# Fuente.net
KiCad netlist of a schematic drawn in Altium Designer
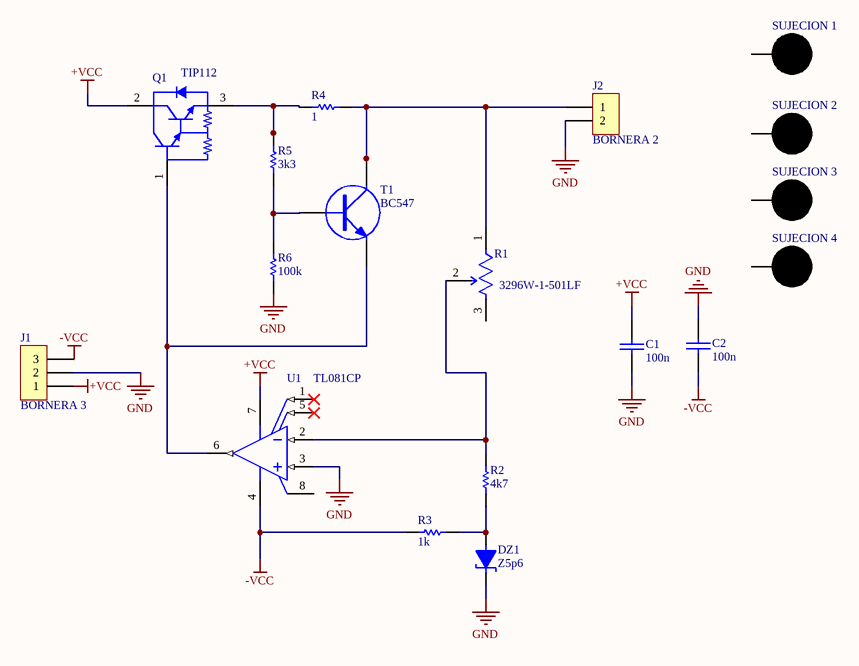
[diagram p0: Fuente.SchDoc]

(export (version "E")
  (design (tool "Eeschema 10.0.6"))
  (components
    (comp (ref "C1") (value "100n") (footprint "CAP200") (libsource (lib "LIB PIO IX") (part "CAP")))
    (comp (ref "C2") (value "100n") (footprint "CAP200") (libsource (lib "LIB PIO IX") (part "CAP")))
    (comp (ref "DZ1") (value "Z5p6") (footprint "DO41") (libsource (lib "LIB PIO IX") (part "DIODO ZENER")))
    (comp (ref "J1")
      (value "BORNERA 3")
      (footprint "BORNERA3")
      (libsource (lib "LIB PIO IX") (part "BORNERA 3"))
    )
    (comp (ref "J2")
      (value "BORNERA 2")
      (footprint "BORNERA2")
      (libsource (lib "LIB PIO IX") (part "BORNERA 2"))
    )
    (comp (ref "Q1")
      (value "TIP112")
      (footprint "ONSC-TO-220-3-221A-09")
      (description "Plastic Medium-Power, Complementary Silicon Transistor, 3-Pin TO-220, Tube")
      (fields (field (name "MANUFACTURER") "On Semiconductor"))
      (libsource (lib "Altium Content Vault") (part "ONSC-DT-NPN-B1C2E3-3_A"))
    )
    (comp (ref "R1")
      (value "3296W-1-501LF")
      (footprint "FP-3296W-MFG")
      (description "TRIMMER 500 OHM 0.5W PC PIN TOP")
      (fields (field (name "TOLERANCE") "10%"))
      (libsource (lib "Altium Content Vault") (part "2dcfd2547301a7d3209a5e99acfd772"))
    )
    (comp (ref "R2") (value "4k7") (footprint "RES400") (libsource (lib "LIB PIO IX") (part "RES")))
    (comp (ref "R3") (value "1k") (footprint "RES400") (libsource (lib "LIB PIO IX") (part "RES")))
    (comp (ref "R4") (value "1") (footprint "RES600") (libsource (lib "LIB PIO IX") (part "RES")))
    (comp (ref "R5") (value "3k3") (footprint "RES400") (libsource (lib "LIB PIO IX") (part "RES")))
    (comp (ref "R6") (value "100k") (footprint "RES400") (libsource (lib "LIB PIO IX") (part "RES")))
    (comp (ref "SUJECION 1")
      (value "~")
      (footprint "SUJECION (5.00MM - 3.50MM)")
      (libsource (lib "LIB2013") (part "SUJECION"))
    )
    (comp (ref "SUJECION 2")
      (value "~")
      (footprint "SUJECION (5.00MM - 3.50MM)")
      (libsource (lib "LIB2013") (part "SUJECION"))
    )
    (comp (ref "SUJECION 3")
      (value "~")
      (footprint "SUJECION (5.00MM - 3.50MM)")
      (libsource (lib "LIB2013") (part "SUJECION"))
    )
    (comp (ref "SUJECION 4")
      (value "~")
      (footprint "SUJECION (5.00MM - 3.50MM)")
      (libsource (lib "LIB2013") (part "SUJECION"))
    )
    (comp (ref "T1")
      (value "BC547")
      (footprint "TO92")
      (libsource (lib "LIB PIO IX") (part "TRANSISTOR NPN"))
    )
    (comp (ref "U1")
      (value "TL081CP")
      (footprint "P0008A")
      (description "JFET-Input Operational Amplifier, 7 to 36 V, 0 to 70 degC, 8-pin DIP (P8), Pb-Free (RoHS)")
      (fields (field (name "MANUFACTURER") "Texas Instruments"))
      (libsource (lib "Altium Content Vault") (part "TI-AMP-S5-2-8"))
    )
  )
  (nets
    (net (code "1") (name "+VCC") (class "Default")
      (node (ref "C1") (pin "1") (pinfunction "1_1") (pintype "passive"))
      (node (ref "J1") (pin "1") (pinfunction "1_1") (pintype "passive"))
      (node (ref "Q1") (pin "2") (pinfunction "C_2") (pintype "passive"))
      (node (ref "U1") (pin "7") (pinfunction "VCC+_7") (pintype "power_in"))
    )
    (net (code "2") (name "-VCC") (class "Default")
      (node (ref "C2") (pin "2") (pinfunction "2_2") (pintype "passive"))
      (node (ref "J1") (pin "3") (pinfunction "3_3") (pintype "passive"))
      (node (ref "R3") (pin "1") (pinfunction "1_1") (pintype "passive"))
      (node (ref "U1") (pin "4") (pinfunction "VCC-_4") (pintype "power_in"))
    )
    (net (code "3") (name "GND") (class "Default")
      (node (ref "C1") (pin "2") (pinfunction "2_2") (pintype "passive"))
      (node (ref "C2") (pin "1") (pinfunction "1_1") (pintype "passive"))
      (node (ref "DZ1") (pin "2") (pinfunction "2_2") (pintype "passive"))
      (node (ref "J1") (pin "2") (pinfunction "2_2") (pintype "passive"))
      (node (ref "J2") (pin "2") (pinfunction "2_2") (pintype "passive"))
      (node (ref "R6") (pin "1") (pinfunction "1_1") (pintype "passive"))
      (node (ref "U1") (pin "3") (pinfunction "IN+_3") (pintype "input"))
    )
    (net (code "4") (name "Net-(DZ1-Pad1)") (class "Default")
      (node (ref "DZ1") (pin "1") (pinfunction "1_1") (pintype "passive"))
      (node (ref "R2") (pin "2") (pinfunction "2_2") (pintype "passive"))
      (node (ref "R3") (pin "2") (pinfunction "2_2") (pintype "passive"))
    )
    (net (code "5") (name "Net-(Q1-B)") (class "Default")
      (node (ref "Q1") (pin "1") (pinfunction "B_1") (pintype "passive"))
      (node (ref "T1") (pin "3") (pinfunction "E_3") (pintype "passive"))
      (node (ref "U1") (pin "6") (pinfunction "OUT_6") (pintype "output"))
    )
    (net (code "6") (name "Net-(Q1-E)") (class "Default")
      (node (ref "Q1") (pin "3") (pinfunction "E_3") (pintype "passive"))
      (node (ref "R4") (pin "2") (pinfunction "2_2") (pintype "passive"))
      (node (ref "R5") (pin "2") (pinfunction "2_2") (pintype "passive"))
    )
    (net (code "7") (name "Net-(R1-CCW)") (class "Default")
      (node (ref "J2") (pin "1") (pinfunction "1_1") (pintype "passive"))
      (node (ref "R1") (pin "1") (pinfunction "CCW_1") (pintype "passive"))
      (node (ref "R4") (pin "1") (pinfunction "1_1") (pintype "passive"))
      (node (ref "T1") (pin "2") (pinfunction "C_2") (pintype "passive"))
    )
    (net (code "8") (name "Net-(R1-WIPER)") (class "Default")
      (node (ref "R1") (pin "2") (pinfunction "WIPER_2") (pintype "passive"))
      (node (ref "R2") (pin "1") (pinfunction "1_1") (pintype "passive"))
      (node (ref "U1") (pin "2") (pinfunction "IN-_2") (pintype "input"))
    )
    (net (code "9") (name "Net-(T1-B)") (class "Default")
      (node (ref "R5") (pin "1") (pinfunction "1_1") (pintype "passive"))
      (node (ref "R6") (pin "2") (pinfunction "2_2") (pintype "passive"))
      (node (ref "T1") (pin "1") (pinfunction "B_1") (pintype "passive"))
    )
    (net (code "10") (name "unconnected-(R1-CW-Pad3)") (class "Default")
      (node (ref "R1") (pin "3") (pinfunction "CW_3") (pintype "passive"))
    )
    (net (code "11") (name "unconnected-(SUJECION 1-Pad1)") (class "Default")
      (node (ref "SUJECION 1") (pin "1") (pinfunction "1_1") (pintype "passive"))
    )
    (net (code "12") (name "unconnected-(SUJECION 2-Pad1)") (class "Default")
      (node (ref "SUJECION 2") (pin "1") (pinfunction "1_1") (pintype "passive"))
    )
    (net (code "13") (name "unconnected-(SUJECION 3-Pad1)") (class "Default")
      (node (ref "SUJECION 3") (pin "1") (pinfunction "1_1") (pintype "passive"))
    )
    (net (code "14") (name "unconnected-(SUJECION 4-Pad1)") (class "Default")
      (node (ref "SUJECION 4") (pin "1") (pinfunction "1_1") (pintype "passive"))
    )
    (net (code "15") (name "unconnected-(U1-NC-Pad8)") (class "Default")
      (node (ref "U1") (pin "8") (pinfunction "NC_8") (pintype "passive"))
    )
    (net (code "16") (name "unconnected-(U1-OFFSET_N1-Pad1)") (class "Default")
      (node (ref "U1") (pin "1") (pinfunction "OFFSET_N1_1") (pintype "input+no_connect"))
    )
    (net (code "17") (name "unconnected-(U1-OFFSET_N2-Pad5)") (class "Default")
      (node (ref "U1") (pin "5") (pinfunction "OFFSET_N2_5") (pintype "input+no_connect"))
    )
  )
)
